# WLED_01_v0_9.net
KiCad netlist of a schematic drawn in EAGLE
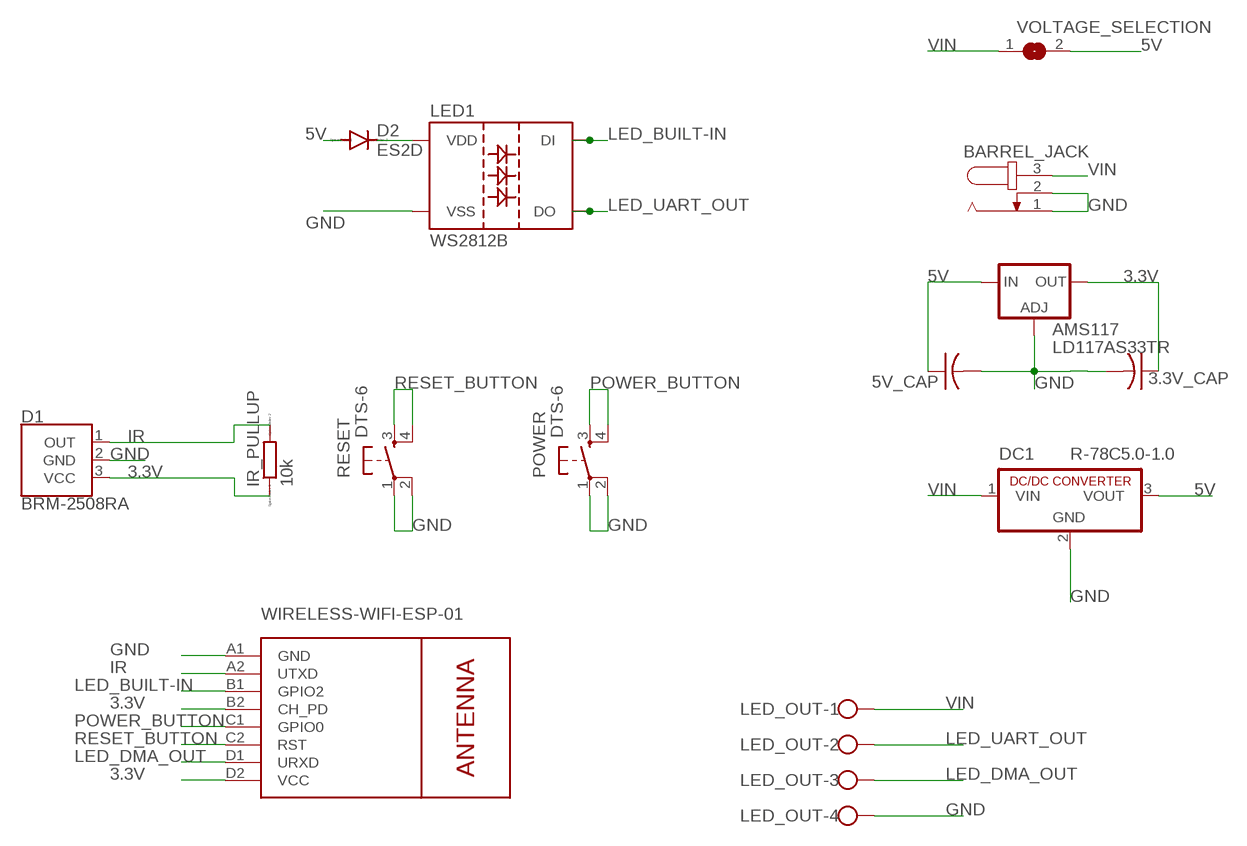
[diagram p0: schematic, sheet 1]

(export (version "E")
  (design (tool "Eeschema 10.0.6"))
  (components
    (comp (ref "3.3V_CAP")
      (value "C-USC0805K")
      (footprint "eagle-import:C0805K")
      (libsource (lib "eagle-import") (part "C-USC0805K"))
    )
    (comp (ref "5V_CAP")
      (value "C-USC0805K")
      (footprint "eagle-import:C0805K")
      (libsource (lib "eagle-import") (part "C-USC0805K"))
    )
    (comp (ref "AMS117")
      (value "LD117AS33TR")
      (footprint "eagle-import:SOT223")
      (libsource (lib "eagle-import") (part "LD117A?S33TR"))
    )
    (comp (ref "BARREL_JACK")
      (value "JACK-PLUG0")
      (footprint "eagle-import:SPC4077")
      (libsource (lib "eagle-import") (part "JACK-PLUG0"))
    )
    (comp (ref "D1")
      (value "BRM-2508RA")
      (footprint "eagle-import:BRM-2508")
      (libsource (lib "eagle-import") (part "BRM-2508RA"))
    )
    (comp (ref "D2")
      (value "ES2D")
      (footprint "eagle-import:SMB")
      (libsource (lib "eagle-import") (part "ES2D"))
    )
    (comp (ref "DC1")
      (value "R-78C5.0-1.0")
      (footprint "eagle-import:SIP3")
      (libsource (lib "eagle-import") (part "R-78C-1.05.0"))
    )
    (comp (ref "IR_PULLUP")
      (value "10k")
      (footprint "eagle-import:R0603")
      (libsource (lib "eagle-import") (part "RR0603"))
    )
    (comp (ref "LED1")
      (value "WS2812B")
      (footprint "eagle-import:WS2812B")
      (libsource (lib "eagle-import") (part "WS2812B"))
    )
    (comp (ref "LED_OUT")
      (value "W237-4")
      (footprint "eagle-import:W237-4")
      (libsource (lib "eagle-import") (part "W237-4"))
    )
    (comp (ref "POWER")
      (value "DTS-6")
      (footprint "eagle-import:DTS-6")
      (libsource (lib "eagle-import") (part "DTS-6"))
    )
    (comp (ref "RESET")
      (value "DTS-6")
      (footprint "eagle-import:DTS-6")
      (libsource (lib "eagle-import") (part "DTS-6"))
    )
    (comp (ref "U$1")
      (value "WIRELESS-WIFI-ESP-01")
      (footprint "eagle-import:WIRELESS-WIFI-ESP-01")
      (libsource (lib "eagle-import") (part "WIRELESS-WIFI-ESP-01"))
    )
    (comp (ref "VOLTAGE_SELECTION")
      (value "SJ")
      (footprint "eagle-import:SJ")
      (libsource (lib "eagle-import") (part "SJ"))
    )
  )
  (nets
    (net (code "1") (name "/3.3V") (class "Default")
      (node (ref "3.3V_CAP") (pin "1") (pinfunction "1_1") (pintype "passive"))
      (node (ref "AMS117") (pin "4") (pinfunction "OUT_4") (pintype "passive"))
      (node (ref "D1") (pin "3") (pinfunction "VCC_3") (pintype "bidirectional"))
      (node (ref "IR_PULLUP") (pin "1") (pinfunction "1_1") (pintype "passive"))
      (node (ref "U$1") (pin "B2") (pinfunction "CH_PD_B2") (pintype "bidirectional"))
      (node (ref "U$1") (pin "D2") (pinfunction "VCC_D2") (pintype "power_in"))
    )
    (net (code "2") (name "/5V") (class "Default")
      (node (ref "5V_CAP") (pin "1") (pinfunction "1_1") (pintype "passive"))
      (node (ref "AMS117") (pin "3") (pinfunction "IN_3") (pintype "input"))
      (node (ref "D2") (pin "A") (pinfunction "A_A") (pintype "passive"))
      (node (ref "DC1") (pin "3") (pinfunction "VOUT_3") (pintype "passive"))
      (node (ref "VOLTAGE_SELECTION") (pin "2") (pinfunction "2_2") (pintype "passive"))
    )
    (net (code "3") (name "/GND") (class "Default")
      (node (ref "3.3V_CAP") (pin "2") (pinfunction "2_2") (pintype "passive"))
      (node (ref "5V_CAP") (pin "2") (pinfunction "2_2") (pintype "passive"))
      (node (ref "AMS117") (pin "1") (pinfunction "ADJ_1") (pintype "input"))
      (node (ref "BARREL_JACK") (pin "1") (pinfunction "1_1") (pintype "passive"))
      (node (ref "BARREL_JACK") (pin "2") (pinfunction "2_2") (pintype "passive"))
      (node (ref "D1") (pin "2") (pinfunction "GND_2") (pintype "bidirectional"))
      (node (ref "DC1") (pin "2") (pinfunction "GND_2") (pintype "passive"))
      (node (ref "LED1") (pin "3") (pinfunction "VSS_3") (pintype "bidirectional"))
      (node (ref "LED_OUT") (pin "4") (pinfunction "KL_4") (pintype "passive"))
      (node (ref "POWER") (pin "1") (pinfunction "1_1") (pintype "passive"))
      (node (ref "POWER") (pin "2") (pinfunction "2_2") (pintype "passive"))
      (node (ref "RESET") (pin "1") (pinfunction "1_1") (pintype "passive"))
      (node (ref "RESET") (pin "2") (pinfunction "2_2") (pintype "passive"))
      (node (ref "U$1") (pin "A1") (pinfunction "GND_A1") (pintype "power_in"))
    )
    (net (code "4") (name "/IR") (class "Default")
      (node (ref "D1") (pin "1") (pinfunction "OUT_1") (pintype "bidirectional"))
      (node (ref "IR_PULLUP") (pin "2") (pinfunction "2_2") (pintype "passive"))
      (node (ref "U$1") (pin "A2") (pinfunction "UTXD_A2") (pintype "bidirectional"))
    )
    (net (code "5") (name "/LED_BUILT-IN") (class "Default")
      (node (ref "LED1") (pin "4") (pinfunction "DI_4") (pintype "bidirectional"))
      (node (ref "U$1") (pin "B1") (pinfunction "GPIO2_B1") (pintype "bidirectional"))
    )
    (net (code "6") (name "/LED_DMA_OUT") (class "Default")
      (node (ref "LED_OUT") (pin "3") (pinfunction "KL_3") (pintype "passive"))
      (node (ref "U$1") (pin "D1") (pinfunction "URXD_D1") (pintype "bidirectional"))
    )
    (net (code "7") (name "/LED_UART_OUT") (class "Default")
      (node (ref "LED1") (pin "2") (pinfunction "DO_2") (pintype "bidirectional"))
      (node (ref "LED_OUT") (pin "2") (pinfunction "KL_2") (pintype "passive"))
    )
    (net (code "8") (name "/POWER_BUTTON") (class "Default")
      (node (ref "POWER") (pin "3") (pinfunction "3_3") (pintype "passive"))
      (node (ref "POWER") (pin "4") (pinfunction "4_4") (pintype "passive"))
      (node (ref "U$1") (pin "C1") (pinfunction "GPIO0_C1") (pintype "bidirectional"))
    )
    (net (code "9") (name "/RESET_BUTTON") (class "Default")
      (node (ref "RESET") (pin "3") (pinfunction "3_3") (pintype "passive"))
      (node (ref "RESET") (pin "4") (pinfunction "4_4") (pintype "passive"))
      (node (ref "U$1") (pin "C2") (pinfunction "RST_C2") (pintype "bidirectional"))
    )
    (net (code "10") (name "/VIN") (class "Default")
      (node (ref "BARREL_JACK") (pin "3") (pinfunction "3_3") (pintype "passive"))
      (node (ref "DC1") (pin "1") (pinfunction "VIN_1") (pintype "passive"))
      (node (ref "LED_OUT") (pin "1") (pinfunction "KL_1") (pintype "passive"))
      (node (ref "VOLTAGE_SELECTION") (pin "1") (pinfunction "1_1") (pintype "passive"))
    )
    (net (code "11") (name "Net-(LED1-VDD)") (class "Default")
      (node (ref "D2") (pin "C") (pinfunction "C_C") (pintype "passive"))
      (node (ref "LED1") (pin "1") (pinfunction "VDD_1") (pintype "bidirectional"))
    )
  )
)
